# EPS_Battery_Controller_RLCL.net
KiCad netlist of a schematic drawn in Altium Designer
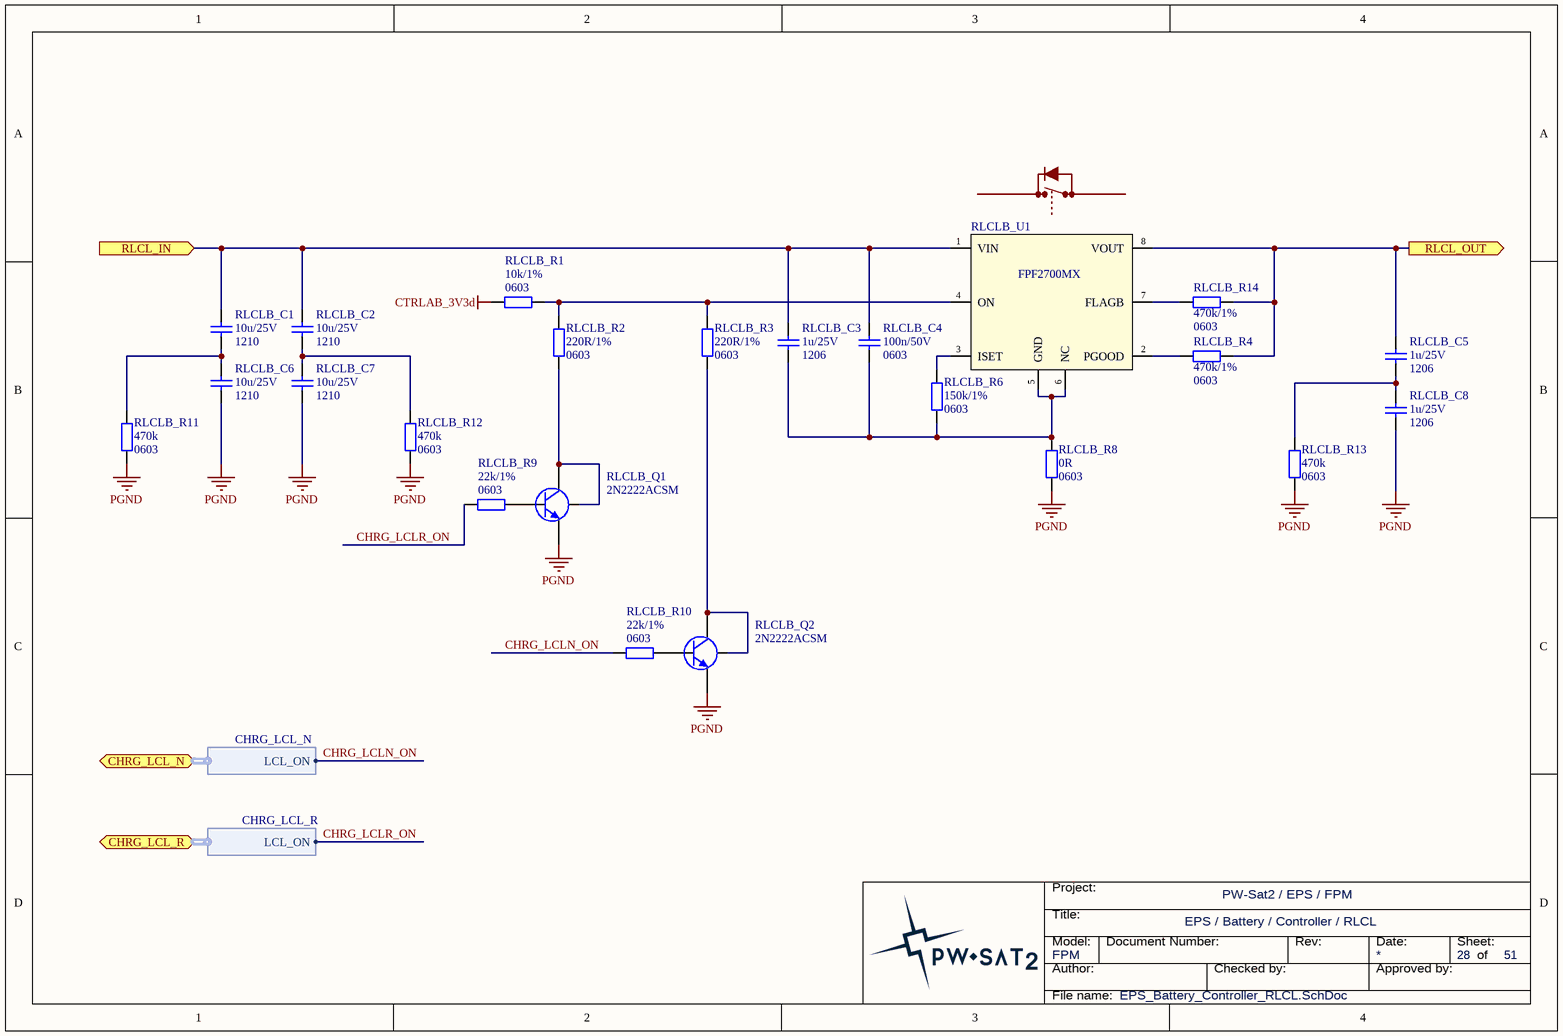
[diagram p0: EPS_Battery_Controller_RLCL.SchDoc]

(export (version "E")
  (design (tool "Eeschema 10.0.6"))
  (components
    (comp (ref "RLCLB_C1")
      (value "10u/25V")
      (footprint "SMD_Capacitor_1210")
      (description "Ceramic Cap Murata Automotive 10u/25V X7R 1210")
      (fields
        (field (name "MANUFACTURER") "Murata")
        (field (name "MANUFACTURERPARTNUMBER") "GCJ32ER71E106KA12L")
        (field (name "PACKAGE") "1210")
      )
      (libsource (lib "capacitors") (part "Cer_GCJ32ER71E106KA12L"))
    )
    (comp (ref "RLCLB_C2")
      (value "10u/25V")
      (footprint "SMD_Capacitor_1210")
      (description "Ceramic Cap Murata Automotive 10u/25V X7R 1210")
      (fields
        (field (name "MANUFACTURER") "Murata")
        (field (name "MANUFACTURERPARTNUMBER") "GCJ32ER71E106KA12L")
        (field (name "PACKAGE") "1210")
      )
      (libsource (lib "capacitors") (part "Cer_GCJ32ER71E106KA12L"))
    )
    (comp (ref "RLCLB_C3")
      (value "1u/25V")
      (footprint "SMD_Capacitor_1206")
      (description "Ceramic Cap Kemet COTS 1u/25V X7R 1206")
      (fields
        (field (name "MANUFACTURERPARTNUMBER") "C1206T105K3RALTU")
        (field (name "MANUFACTURER") "Kemet")
        (field (name "PACKAGE") "1206")
      )
      (libsource (lib "capacitors") (part "Cer_C1206T105K3RALTU"))
    )
    (comp (ref "RLCLB_C4")
      (value "100n/50V")
      (footprint "SMD_Capacitor_0603")
      (description "Ceramic Cap Murata Automotive 100n/50V X7R 0603")
      (fields
        (field (name "MANUFACTURER") "Murata")
        (field (name "MANUFACTURERPARTNUMBER") "GCJ188R71H104KA12D")
        (field (name "PACKAGE") "0603")
      )
      (libsource (lib "capacitors") (part "Cer_GCJ188R71H104KA12D"))
    )
    (comp (ref "RLCLB_C5")
      (value "1u/25V")
      (footprint "SMD_Capacitor_1206")
      (description "Ceramic Cap Kemet COTS 1u/25V X7R 1206")
      (fields
        (field (name "MANUFACTURERPARTNUMBER") "C1206T105K3RALTU")
        (field (name "MANUFACTURER") "Kemet")
        (field (name "PACKAGE") "1206")
      )
      (libsource (lib "capacitors") (part "Cer_C1206T105K3RALTU"))
    )
    (comp (ref "RLCLB_C6")
      (value "10u/25V")
      (footprint "SMD_Capacitor_1210")
      (description "Ceramic Cap Murata Automotive 10u/25V X7R 1210")
      (fields
        (field (name "MANUFACTURER") "Murata")
        (field (name "MANUFACTURERPARTNUMBER") "GCJ32ER71E106KA12L")
        (field (name "PACKAGE") "1210")
      )
      (libsource (lib "capacitors") (part "Cer_GCJ32ER71E106KA12L"))
    )
    (comp (ref "RLCLB_C7")
      (value "10u/25V")
      (footprint "SMD_Capacitor_1210")
      (description "Ceramic Cap Murata Automotive 10u/25V X7R 1210")
      (fields
        (field (name "MANUFACTURER") "Murata")
        (field (name "MANUFACTURERPARTNUMBER") "GCJ32ER71E106KA12L")
        (field (name "PACKAGE") "1210")
      )
      (libsource (lib "capacitors") (part "Cer_GCJ32ER71E106KA12L"))
    )
    (comp (ref "RLCLB_C8")
      (value "1u/25V")
      (footprint "SMD_Capacitor_1206")
      (description "Ceramic Cap Kemet COTS 1u/25V X7R 1206")
      (fields
        (field (name "MANUFACTURERPARTNUMBER") "C1206T105K3RALTU")
        (field (name "MANUFACTURER") "Kemet")
        (field (name "PACKAGE") "1206")
      )
      (libsource (lib "capacitors") (part "Cer_C1206T105K3RALTU"))
    )
    (comp (ref "RLCLB_Q1")
      (value "2N2222ACSM")
      (footprint "LCC1-4_BEC")
      (description "Silicon Planar Epitaxial NPN Transistor.")
      (fields (field (name "MANUFACTURER") "Semelab-TT"))
      (libsource (lib "transistors") (part "2N2222ACSM"))
    )
    (comp (ref "RLCLB_Q2")
      (value "2N2222ACSM")
      (footprint "LCC1-4_BEC")
      (description "Silicon Planar Epitaxial NPN Transistor.")
      (fields (field (name "MANUFACTURER") "Semelab-TT"))
      (libsource (lib "transistors") (part "2N2222ACSM"))
    )
    (comp (ref "RLCLB_R1")
      (value "10k/1%")
      (footprint "SMD_Resistor_0603")
      (fields (field (name "PACKAGE") "0603"))
      (libsource (lib "resistors") (part "Res"))
    )
    (comp (ref "RLCLB_R2")
      (value "220R/1%")
      (footprint "SMD_Resistor_0603")
      (fields (field (name "PACKAGE") "0603"))
      (libsource (lib "resistors") (part "Res"))
    )
    (comp (ref "RLCLB_R3")
      (value "220R/1%")
      (footprint "SMD_Resistor_0603")
      (fields (field (name "PACKAGE") "0603"))
      (libsource (lib "resistors") (part "Res"))
    )
    (comp (ref "RLCLB_R4")
      (value "470k/1%")
      (footprint "SMD_Resistor_0603")
      (fields (field (name "PACKAGE") "0603"))
      (libsource (lib "") (part "Res_2"))
    )
    (comp (ref "RLCLB_R6")
      (value "150k/1%")
      (footprint "SMD_Resistor_0603")
      (fields (field (name "PACKAGE") "0603"))
      (libsource (lib "resistors") (part "Res"))
    )
    (comp (ref "RLCLB_R8")
      (value "0R")
      (footprint "SMD_Resistor_0603")
      (fields (field (name "PACKAGE") "0603"))
      (libsource (lib "resistors") (part "Res"))
    )
    (comp (ref "RLCLB_R9")
      (value "22k/1%")
      (footprint "SMD_Resistor_0603")
      (fields (field (name "PACKAGE") "0603"))
      (libsource (lib "") (part "Res_1"))
    )
    (comp (ref "RLCLB_R10")
      (value "22k/1%")
      (footprint "SMD_Resistor_0603")
      (fields (field (name "PACKAGE") "0603"))
      (libsource (lib "") (part "Res_1"))
    )
    (comp (ref "RLCLB_R11")
      (value "470k")
      (footprint "SMD_Resistor_0603")
      (fields (field (name "PACKAGE") "0603"))
      (libsource (lib "resistors") (part "Res"))
    )
    (comp (ref "RLCLB_R12")
      (value "470k")
      (footprint "SMD_Resistor_0603")
      (fields (field (name "PACKAGE") "0603"))
      (libsource (lib "resistors") (part "Res"))
    )
    (comp (ref "RLCLB_R13")
      (value "470k")
      (footprint "SMD_Resistor_0603")
      (fields (field (name "PACKAGE") "0603"))
      (libsource (lib "resistors") (part "Res"))
    )
    (comp (ref "RLCLB_R14")
      (value "470k/1%")
      (footprint "SMD_Resistor_0603")
      (fields (field (name "PACKAGE") "0603"))
      (libsource (lib "") (part "Res_2"))
    )
    (comp (ref "RLCLB_U1")
      (value "FPF2700MX")
      (footprint "SOIC-8-N")
      (description "Adj over-current protection 0.4-2A, Load Switch")
      (fields (field (name "MANUFACTURER") "Fairchild Semiconductor"))
      (libsource (lib "microcircuits") (part "FPF2700MX"))
    )
  )
  (nets
    (net (code "3") (name "/CHRG_LCLN_ON") (class "Default")
      (node (ref "RLCLB_R10") (pin "1") (pinfunction "1_1") (pintype "passive"))
    )
    (net (code "4") (name "/CHRG_LCLR_ON") (class "Default")
      (node (ref "RLCLB_R9") (pin "1") (pinfunction "1_1") (pintype "passive"))
    )
    (net (code "5") (name "/RLCL_IN") (class "Default")
      (node (ref "RLCLB_C1") (pin "1") (pinfunction "1_1") (pintype "passive"))
      (node (ref "RLCLB_C2") (pin "1") (pinfunction "1_1") (pintype "passive"))
      (node (ref "RLCLB_C3") (pin "1") (pinfunction "1_1") (pintype "passive"))
      (node (ref "RLCLB_C4") (pin "1") (pinfunction "1_1") (pintype "passive"))
      (node (ref "RLCLB_U1") (pin "1") (pinfunction "VIN_1") (pintype "passive"))
    )
    (net (code "6") (name "/RLCL_OUT") (class "Default")
      (node (ref "RLCLB_C5") (pin "1") (pinfunction "1_1") (pintype "passive"))
      (node (ref "RLCLB_R14") (pin "2") (pinfunction "2_2") (pintype "passive"))
      (node (ref "RLCLB_R4") (pin "2") (pinfunction "2_2") (pintype "passive"))
      (node (ref "RLCLB_U1") (pin "8") (pinfunction "VOUT_8") (pintype "passive"))
    )
    (net (code "9") (name "CTRLAB_3V3d") (class "Default")
      (node (ref "RLCLB_R1") (pin "2") (pinfunction "2_2") (pintype "passive"))
    )
    (net (code "10") (name "Net-(RLCLB_C1-Pad2)") (class "Default")
      (node (ref "RLCLB_C1") (pin "2") (pinfunction "2_2") (pintype "passive"))
      (node (ref "RLCLB_C6") (pin "1") (pinfunction "1_1") (pintype "passive"))
      (node (ref "RLCLB_R11") (pin "1") (pinfunction "1_1") (pintype "passive"))
    )
    (net (code "11") (name "Net-(RLCLB_C2-Pad2)") (class "Default")
      (node (ref "RLCLB_C2") (pin "2") (pinfunction "2_2") (pintype "passive"))
      (node (ref "RLCLB_C7") (pin "1") (pinfunction "1_1") (pintype "passive"))
      (node (ref "RLCLB_R12") (pin "1") (pinfunction "1_1") (pintype "passive"))
    )
    (net (code "12") (name "Net-(RLCLB_C5-Pad2)") (class "Default")
      (node (ref "RLCLB_C5") (pin "2") (pinfunction "2_2") (pintype "passive"))
      (node (ref "RLCLB_C8") (pin "1") (pinfunction "1_1") (pintype "passive"))
      (node (ref "RLCLB_R13") (pin "1") (pinfunction "1_1") (pintype "passive"))
    )
    (net (code "13") (name "Net-(RLCLB_Q1-PadB)") (class "Default")
      (node (ref "RLCLB_Q1") (pin "B") (pinfunction "B_B") (pintype "passive"))
      (node (ref "RLCLB_R9") (pin "2") (pinfunction "2_2") (pintype "passive"))
    )
    (net (code "14") (name "Net-(RLCLB_Q1-PadC)") (class "Default")
      (node (ref "RLCLB_Q1") (pin "C") (pinfunction "C_C") (pintype "passive"))
      (node (ref "RLCLB_Q1") (pin "Shield") (pinfunction "Shield_Shield") (pintype "passive"))
      (node (ref "RLCLB_R2") (pin "2") (pinfunction "2_2") (pintype "passive"))
    )
    (net (code "15") (name "Net-(RLCLB_Q2-PadB)") (class "Default")
      (node (ref "RLCLB_Q2") (pin "B") (pinfunction "B_B") (pintype "passive"))
      (node (ref "RLCLB_R10") (pin "2") (pinfunction "2_2") (pintype "passive"))
    )
    (net (code "16") (name "Net-(RLCLB_Q2-PadC)") (class "Default")
      (node (ref "RLCLB_Q2") (pin "C") (pinfunction "C_C") (pintype "passive"))
      (node (ref "RLCLB_Q2") (pin "Shield") (pinfunction "Shield_Shield") (pintype "passive"))
      (node (ref "RLCLB_R3") (pin "2") (pinfunction "2_2") (pintype "passive"))
    )
    (net (code "17") (name "Net-(RLCLB_U1-FLAGB)") (class "Default")
      (node (ref "RLCLB_R14") (pin "1") (pinfunction "1_1") (pintype "passive"))
      (node (ref "RLCLB_U1") (pin "7") (pinfunction "FLAGB_7") (pintype "passive"))
    )
    (net (code "18") (name "Net-(RLCLB_U1-GND)") (class "Default")
      (node (ref "RLCLB_C3") (pin "2") (pinfunction "2_2") (pintype "passive"))
      (node (ref "RLCLB_C4") (pin "2") (pinfunction "2_2") (pintype "passive"))
      (node (ref "RLCLB_R6") (pin "2") (pinfunction "2_2") (pintype "passive"))
      (node (ref "RLCLB_R8") (pin "1") (pinfunction "1_1") (pintype "passive"))
      (node (ref "RLCLB_U1") (pin "5") (pinfunction "GND_5") (pintype "passive"))
      (node (ref "RLCLB_U1") (pin "6") (pinfunction "NC_6") (pintype "passive"))
    )
    (net (code "19") (name "Net-(RLCLB_U1-ISET)") (class "Default")
      (node (ref "RLCLB_R6") (pin "1") (pinfunction "1_1") (pintype "passive"))
      (node (ref "RLCLB_U1") (pin "3") (pinfunction "ISET_3") (pintype "passive"))
    )
    (net (code "20") (name "Net-(RLCLB_U1-ON)") (class "Default")
      (node (ref "RLCLB_R1") (pin "1") (pinfunction "1_1") (pintype "passive"))
      (node (ref "RLCLB_R2") (pin "1") (pinfunction "1_1") (pintype "passive"))
      (node (ref "RLCLB_R3") (pin "1") (pinfunction "1_1") (pintype "passive"))
      (node (ref "RLCLB_U1") (pin "4") (pinfunction "ON_4") (pintype "passive"))
    )
    (net (code "21") (name "Net-(RLCLB_U1-PGOOD)") (class "Default")
      (node (ref "RLCLB_R4") (pin "1") (pinfunction "1_1") (pintype "passive"))
      (node (ref "RLCLB_U1") (pin "2") (pinfunction "PGOOD_2") (pintype "passive"))
    )
    (net (code "22") (name "PGND") (class "Default")
      (node (ref "RLCLB_C6") (pin "2") (pinfunction "2_2") (pintype "passive"))
      (node (ref "RLCLB_C7") (pin "2") (pinfunction "2_2") (pintype "passive"))
      (node (ref "RLCLB_C8") (pin "2") (pinfunction "2_2") (pintype "passive"))
      (node (ref "RLCLB_Q1") (pin "E") (pinfunction "E_E") (pintype "passive"))
      (node (ref "RLCLB_Q2") (pin "E") (pinfunction "E_E") (pintype "passive"))
      (node (ref "RLCLB_R11") (pin "2") (pinfunction "2_2") (pintype "passive"))
      (node (ref "RLCLB_R12") (pin "2") (pinfunction "2_2") (pintype "passive"))
      (node (ref "RLCLB_R13") (pin "2") (pinfunction "2_2") (pintype "passive"))
      (node (ref "RLCLB_R8") (pin "2") (pinfunction "2_2") (pintype "passive"))
    )
  )
)
